# Tauchlampe.net
KiCad netlist of a schematic drawn in EAGLE
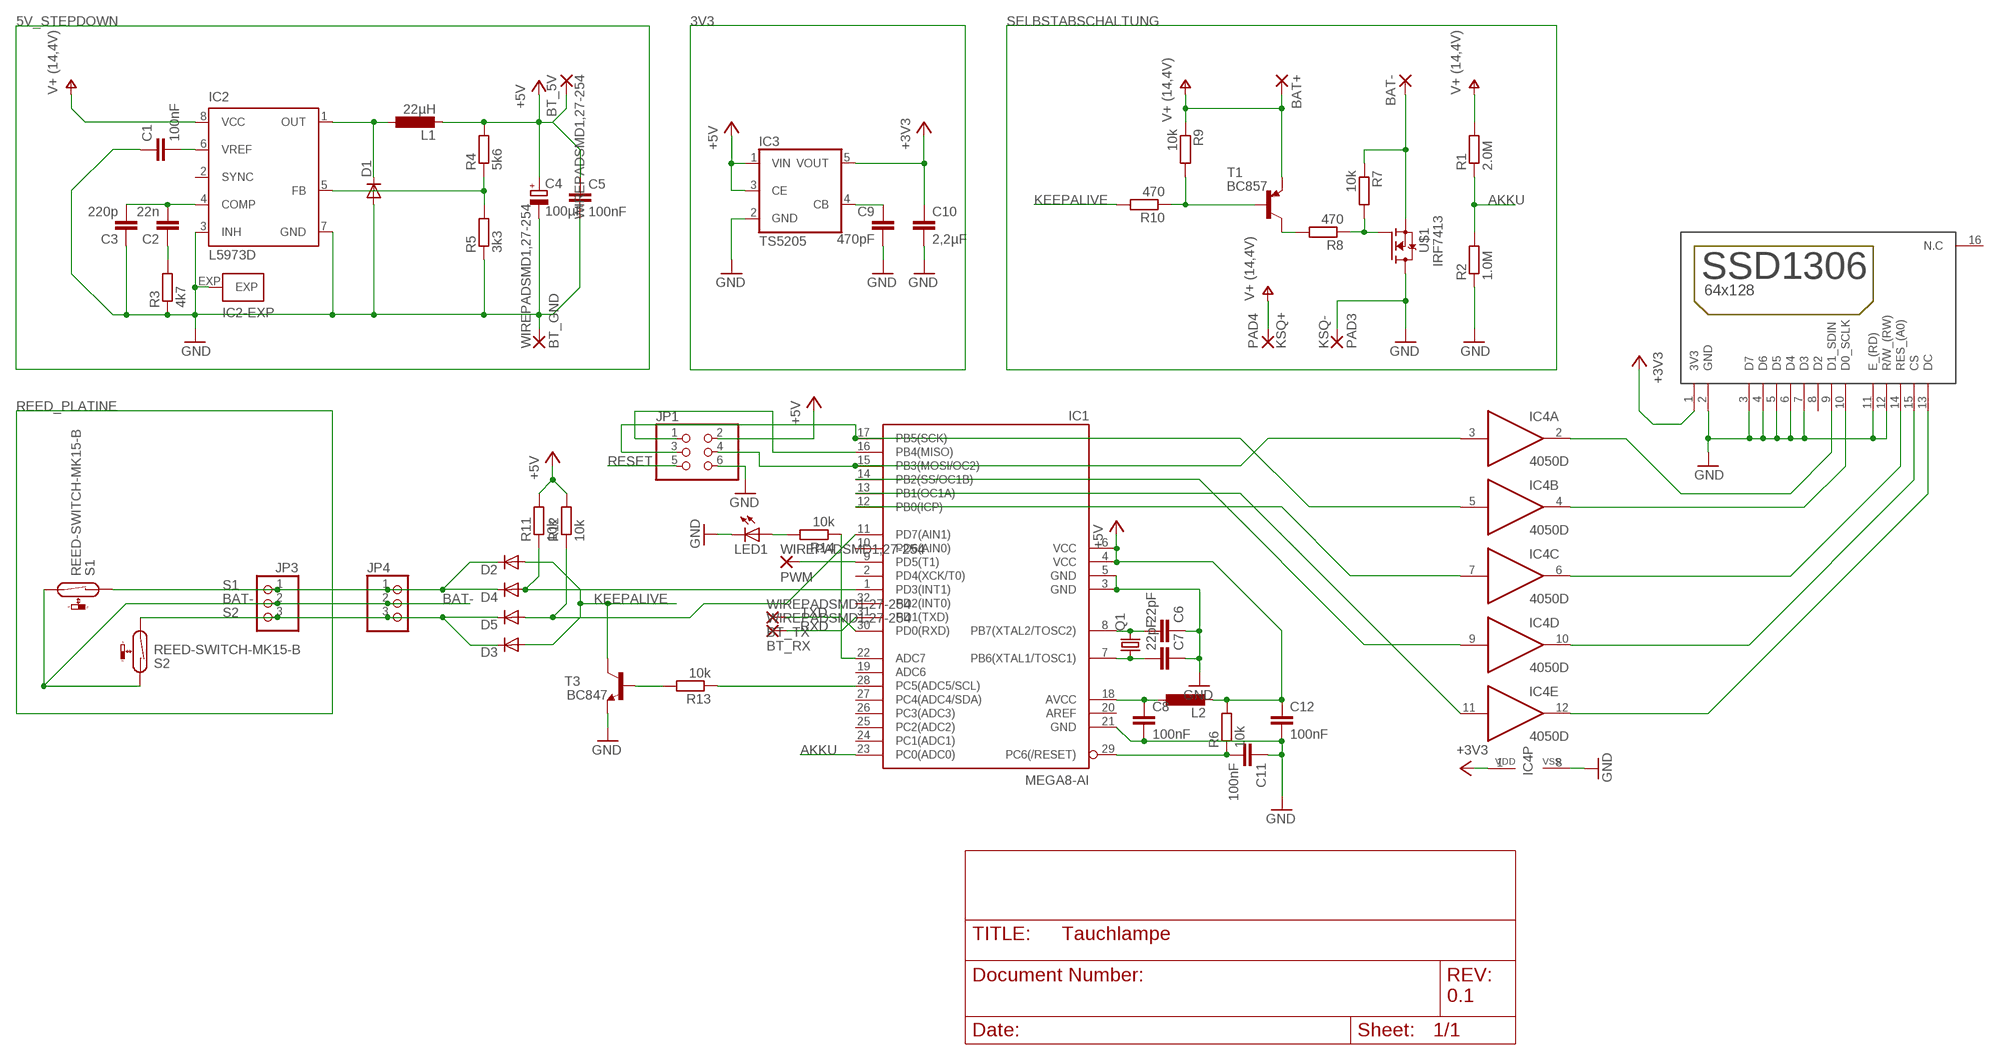
[diagram p0: schematic, sheet 1]

(export (version "E")
  (design (tool "Eeschema 10.0.6"))
  (components
    (comp (ref "BAT+")
      (value "WIREPAD3,81/1,1")
      (footprint "eagle-import:3,81_1,1")
      (libsource (lib "eagle-import") (part "WIREPAD3,81/1,1"))
    )
    (comp (ref "BAT-")
      (value "WIREPAD3,81/1,1")
      (footprint "eagle-import:3,81_1,1")
      (libsource (lib "eagle-import") (part "WIREPAD3,81/1,1"))
    )
    (comp (ref "BT_5V")
      (value "WIREPADSMD1,27-254")
      (footprint "eagle-import:SMD1,27-2,54")
      (libsource (lib "eagle-import") (part "WIREPADSMD1,27-254"))
    )
    (comp (ref "BT_GND")
      (value "WIREPADSMD1,27-254")
      (footprint "eagle-import:SMD1,27-2,54")
      (libsource (lib "eagle-import") (part "WIREPADSMD1,27-254"))
    )
    (comp (ref "BT_RX")
      (value "WIREPADSMD1,27-254")
      (footprint "eagle-import:SMD1,27-2,54")
      (libsource (lib "eagle-import") (part "WIREPADSMD1,27-254"))
    )
    (comp (ref "BT_TX")
      (value "WIREPADSMD1,27-254")
      (footprint "eagle-import:SMD1,27-2,54")
      (libsource (lib "eagle-import") (part "WIREPADSMD1,27-254"))
    )
    (comp (ref "C1")
      (value "100nF")
      (footprint "eagle-import:C0603K")
      (libsource (lib "eagle-import") (part "C-EUC0603K"))
    )
    (comp (ref "C2")
      (value "22n")
      (footprint "eagle-import:C0603K")
      (libsource (lib "eagle-import") (part "C-EUC0603K"))
    )
    (comp (ref "C3")
      (value "220p")
      (footprint "eagle-import:C0603K")
      (libsource (lib "eagle-import") (part "C-EUC0603K"))
    )
    (comp (ref "C4")
      (value "100µF")
      (footprint "eagle-import:153CLV-0505")
      (libsource (lib "eagle-import") (part "CPOL-EU153CLV-0505"))
    )
    (comp (ref "C5")
      (value "100nF")
      (footprint "eagle-import:C1206")
      (libsource (lib "eagle-import") (part "C-EUC1206"))
    )
    (comp (ref "C6")
      (value "22pF")
      (footprint "eagle-import:C1206")
      (libsource (lib "eagle-import") (part "C-EUC1206"))
    )
    (comp (ref "C7")
      (value "22pF")
      (footprint "eagle-import:C1206")
      (libsource (lib "eagle-import") (part "C-EUC1206"))
    )
    (comp (ref "C8")
      (value "100nF")
      (footprint "eagle-import:C0603K")
      (libsource (lib "eagle-import") (part "C-EUC0603K"))
    )
    (comp (ref "C9")
      (value "470pF")
      (footprint "eagle-import:C0603")
      (libsource (lib "eagle-import") (part "C-EUC0603"))
    )
    (comp (ref "C10")
      (value "2,2µF")
      (footprint "eagle-import:C0603")
      (libsource (lib "eagle-import") (part "C-EUC0603"))
    )
    (comp (ref "C11")
      (value "100nF")
      (footprint "eagle-import:C0603K")
      (libsource (lib "eagle-import") (part "C-EUC0603K"))
    )
    (comp (ref "C12")
      (value "100nF")
      (footprint "eagle-import:C0603K")
      (libsource (lib "eagle-import") (part "C-EUC0603K"))
    )
    (comp (ref "D1")
      (value "DIODE-SMB")
      (footprint "eagle-import:SMB")
      (libsource (lib "eagle-import") (part "DIODE-SMB"))
    )
    (comp (ref "D2")
      (value "DIODE-SOD323-W")
      (footprint "eagle-import:SOD323-W")
      (libsource (lib "eagle-import") (part "DIODE-SOD323-W"))
    )
    (comp (ref "D3")
      (value "DIODE-SOD323-W")
      (footprint "eagle-import:SOD323-W")
      (libsource (lib "eagle-import") (part "DIODE-SOD323-W"))
    )
    (comp (ref "D4")
      (value "DIODE-SOD323-W")
      (footprint "eagle-import:SOD323-W")
      (libsource (lib "eagle-import") (part "DIODE-SOD323-W"))
    )
    (comp (ref "D5")
      (value "DIODE-SOD323-W")
      (footprint "eagle-import:SOD323-W")
      (libsource (lib "eagle-import") (part "DIODE-SOD323-W"))
    )
    (comp (ref "IC1")
      (value "MEGA8-AI")
      (footprint "eagle-import:TQFP32-08")
      (fields (field (name "MPN") "ATMEGA8-16AU"))
      (libsource (lib "eagle-import") (part "MEGA8-AI"))
    )
    (comp (ref "IC2")
      (value "L5973D")
      (footprint "eagle-import:HSOP8")
      (fields (field (name "MF") "STMICROELECTRONICS"))
      (libsource (lib "eagle-import") (part "L5973D"))
    )
    (comp (ref "IC3")
      (value "TS5205")
      (footprint "eagle-import:SOT25")
      (libsource (lib "eagle-import") (part "TS5205"))
    )
    (comp (ref "IC4")
      (value "4050D")
      (footprint "eagle-import:SO16")
      (libsource (lib "eagle-import") (part "4050D"))
    )
    (comp (ref "JP1")
      (value "PINHD-2X3")
      (footprint "eagle-import:2X03")
      (libsource (lib "eagle-import") (part "PINHD-2X3"))
    )
    (comp (ref "JP3")
      (value "PINHD-1X03_2.54")
      (footprint "eagle-import:1X03")
      (libsource (lib "eagle-import") (part "PINHD-1X03_2.54"))
    )
    (comp (ref "JP4")
      (value "PINHD-1X03_2.54")
      (footprint "eagle-import:1X03")
      (libsource (lib "eagle-import") (part "PINHD-1X03_2.54"))
    )
    (comp (ref "L1")
      (value "22µH")
      (footprint "eagle-import:PISG")
      (libsource (lib "eagle-import") (part "L-EUPISG"))
    )
    (comp (ref "L2")
      (value "L-EUL2012C")
      (footprint "eagle-import:L2012C")
      (libsource (lib "eagle-import") (part "L-EUL2012C"))
    )
    (comp (ref "LED1")
      (value "LEDCHIP-LED0805")
      (footprint "eagle-import:CHIP-LED0805")
      (libsource (lib "eagle-import") (part "LEDCHIP-LED0805"))
    )
    (comp (ref "PAD3")
      (value "KSQ-")
      (footprint "eagle-import:3,81_1,1")
      (libsource (lib "eagle-import") (part "WIREPAD3,81/1,1"))
    )
    (comp (ref "PAD4")
      (value "KSQ+")
      (footprint "eagle-import:3,81_1,1")
      (libsource (lib "eagle-import") (part "WIREPAD3,81/1,1"))
    )
    (comp (ref "PWM")
      (value "WIREPADSMD1,27-254")
      (footprint "eagle-import:SMD1,27-2,54")
      (libsource (lib "eagle-import") (part "WIREPADSMD1,27-254"))
    )
    (comp (ref "Q1")
      (value "CRYSTALHC49UP")
      (footprint "eagle-import:HC49UP")
      (libsource (lib "eagle-import") (part "CRYSTALHC49UP"))
    )
    (comp (ref "R1")
      (value "2.0M")
      (footprint "eagle-import:M1206")
      (libsource (lib "eagle-import") (part "R-EU_M1206"))
    )
    (comp (ref "R2")
      (value "1.0M")
      (footprint "eagle-import:M1206")
      (libsource (lib "eagle-import") (part "R-EU_M1206"))
    )
    (comp (ref "R3")
      (value "4k7")
      (footprint "eagle-import:R0603")
      (libsource (lib "eagle-import") (part "R-EU_R0603"))
    )
    (comp (ref "R4")
      (value "5k6")
      (footprint "eagle-import:R0603")
      (libsource (lib "eagle-import") (part "R-EU_R0603"))
    )
    (comp (ref "R5")
      (value "3k3")
      (footprint "eagle-import:R0603")
      (libsource (lib "eagle-import") (part "R-EU_R0603"))
    )
    (comp (ref "R6")
      (value "10k")
      (footprint "eagle-import:R1206")
      (libsource (lib "eagle-import") (part "R-EU_R1206"))
    )
    (comp (ref "R7")
      (value "10k")
      (footprint "eagle-import:M0805")
      (libsource (lib "eagle-import") (part "R-EU_M0805"))
    )
    (comp (ref "R8")
      (value "470")
      (footprint "eagle-import:M0805")
      (libsource (lib "eagle-import") (part "R-EU_M0805"))
    )
    (comp (ref "R9")
      (value "10k")
      (footprint "eagle-import:M0805")
      (libsource (lib "eagle-import") (part "R-EU_M0805"))
    )
    (comp (ref "R10")
      (value "470")
      (footprint "eagle-import:M0805")
      (libsource (lib "eagle-import") (part "R-EU_M0805"))
    )
    (comp (ref "R11")
      (value "10k")
      (footprint "eagle-import:M1206")
      (libsource (lib "eagle-import") (part "R-EU_M1206"))
    )
    (comp (ref "R12")
      (value "10k")
      (footprint "eagle-import:M1206")
      (libsource (lib "eagle-import") (part "R-EU_M1206"))
    )
    (comp (ref "R13")
      (value "10k")
      (footprint "eagle-import:M1206")
      (libsource (lib "eagle-import") (part "R-EU_M1206"))
    )
    (comp (ref "R14")
      (value "10k")
      (footprint "eagle-import:M0805")
      (libsource (lib "eagle-import") (part "R-EU_M0805"))
    )
    (comp (ref "S1")
      (value "REED-SWITCH-MK15-B")
      (footprint "eagle-import:MK15")
      (fields (field (name "MF") "MEDER") (field (name "MPN") "MK15-B-2"))
      (libsource (lib "eagle-import") (part "REED-SWITCH-MK15-B"))
    )
    (comp (ref "S2")
      (value "REED-SWITCH-MK15-B")
      (footprint "eagle-import:MK15")
      (fields (field (name "MF") "MEDER") (field (name "MPN") "MK15-B-2"))
      (libsource (lib "eagle-import") (part "REED-SWITCH-MK15-B"))
    )
    (comp (ref "T1")
      (value "BC857")
      (footprint "eagle-import:SOT23-BEC")
      (libsource (lib "eagle-import") (part "-PNP-SOT23-BECBC857A"))
    )
    (comp (ref "T3")
      (value "BC847")
      (footprint "eagle-import:SOT23")
      (libsource (lib "eagle-import") (part "BC847"))
    )
    (comp (ref "U$1")
      (value "IRF7413")
      (footprint "eagle-import:SO-8")
      (libsource (lib "eagle-import") (part "IRF7413"))
    )
    (comp (ref "U$2")
      (value "SDD1306")
      (footprint "eagle-import:2X08")
      (libsource (lib "eagle-import") (part "SDD1306"))
    )
  )
  (nets
    (net (code "1") (name "+3V3") (class "Default")
      (node (ref "C10") (pin "1") (pinfunction "1_1") (pintype "passive"))
      (node (ref "IC3") (pin "5") (pinfunction "VOUT_5") (pintype "passive"))
      (node (ref "IC4") (pin "1") (pinfunction "VDD_1") (pintype "power_in"))
      (node (ref "U$2") (pin "1") (pinfunction "3V3_1") (pintype "bidirectional"))
    )
    (net (code "2") (name "+5V") (class "Default")
      (node (ref "BT_5V") (pin "1") (pinfunction "P_1") (pintype "passive"))
      (node (ref "C12") (pin "1") (pinfunction "1_1") (pintype "passive"))
      (node (ref "C4") (pin "+") (pinfunction "+_+") (pintype "passive"))
      (node (ref "C5") (pin "1") (pinfunction "1_1") (pintype "passive"))
      (node (ref "IC1") (pin "4") (pinfunction "VCC_4") (pintype "power_in"))
      (node (ref "IC1") (pin "6") (pinfunction "VCC_6") (pintype "power_in"))
      (node (ref "IC3") (pin "1") (pinfunction "VIN_1") (pintype "input"))
      (node (ref "IC3") (pin "3") (pinfunction "CE_3") (pintype "input"))
      (node (ref "JP1") (pin "2") (pinfunction "2_2") (pintype "passive"))
      (node (ref "L1") (pin "2") (pinfunction "2_2") (pintype "passive"))
      (node (ref "L2") (pin "2") (pinfunction "2_2") (pintype "passive"))
      (node (ref "R11") (pin "2") (pinfunction "2_2") (pintype "passive"))
      (node (ref "R12") (pin "2") (pinfunction "2_2") (pintype "passive"))
      (node (ref "R4") (pin "2") (pinfunction "2_2") (pintype "passive"))
      (node (ref "R6") (pin "2") (pinfunction "2_2") (pintype "passive"))
    )
    (net (code "5") (name "/AKKU") (class "Default")
      (node (ref "IC1") (pin "23") (pinfunction "PC0(ADC0)_23") (pintype "bidirectional"))
      (node (ref "R1") (pin "1") (pinfunction "1_1") (pintype "passive"))
      (node (ref "R2") (pin "2") (pinfunction "2_2") (pintype "passive"))
    )
    (net (code "6") (name "/BAT-") (class "Default")
      (node (ref "BAT-") (pin "1") (pinfunction "P_1") (pintype "passive"))
      (node (ref "JP3") (pin "2") (pinfunction "2_2") (pintype "passive"))
      (node (ref "JP4") (pin "2") (pinfunction "2_2") (pintype "passive"))
      (node (ref "R7") (pin "1") (pinfunction "1_1") (pintype "passive"))
      (node (ref "S1") (pin "2") (pinfunction "2_2") (pintype "passive"))
      (node (ref "S2") (pin "1") (pinfunction "1_1") (pintype "passive"))
      (node (ref "U$1") (pin "1") (pinfunction "S_1") (pintype "passive"))
      (node (ref "U$1") (pin "2") (pinfunction "S_2") (pintype "passive"))
      (node (ref "U$1") (pin "3") (pinfunction "S_3") (pintype "passive"))
    )
    (net (code "7") (name "/KEEPALIVE") (class "Default")
      (node (ref "D2") (pin "A") (pinfunction "A_A") (pintype "passive"))
      (node (ref "D3") (pin "A") (pinfunction "A_A") (pintype "passive"))
      (node (ref "R10") (pin "2") (pinfunction "2_2") (pintype "passive"))
      (node (ref "T3") (pin "3") (pinfunction "C_3") (pintype "passive"))
    )
    (net (code "9") (name "/RESET") (class "Default")
      (node (ref "C11") (pin "2") (pinfunction "2_2") (pintype "passive"))
      (node (ref "IC1") (pin "29") (pinfunction "PC6(/RESET)_29") (pintype "bidirectional"))
      (node (ref "JP1") (pin "5") (pinfunction "5_5") (pintype "passive"))
      (node (ref "R6") (pin "1") (pinfunction "1_1") (pintype "passive"))
    )
    (net (code "10") (name "/RXD") (class "Default")
      (node (ref "BT_RX") (pin "1") (pinfunction "P_1") (pintype "passive"))
      (node (ref "IC1") (pin "31") (pinfunction "PD1(TXD)_31") (pintype "bidirectional"))
    )
    (net (code "11") (name "/S1") (class "Default")
      (node (ref "D2") (pin "C") (pinfunction "C_C") (pintype "passive"))
      (node (ref "D4") (pin "C") (pinfunction "C_C") (pintype "passive"))
      (node (ref "JP3") (pin "1") (pinfunction "1_1") (pintype "passive"))
      (node (ref "JP4") (pin "1") (pinfunction "1_1") (pintype "passive"))
      (node (ref "S1") (pin "1") (pinfunction "1_1") (pintype "passive"))
    )
    (net (code "12") (name "/S2") (class "Default")
      (node (ref "D3") (pin "C") (pinfunction "C_C") (pintype "passive"))
      (node (ref "D5") (pin "C") (pinfunction "C_C") (pintype "passive"))
      (node (ref "JP3") (pin "3") (pinfunction "3_3") (pintype "passive"))
      (node (ref "JP4") (pin "3") (pinfunction "3_3") (pintype "passive"))
      (node (ref "S2") (pin "2") (pinfunction "2_2") (pintype "passive"))
    )
    (net (code "14") (name "/TXD") (class "Default")
      (node (ref "BT_TX") (pin "1") (pinfunction "P_1") (pintype "passive"))
      (node (ref "IC1") (pin "30") (pinfunction "PD0(RXD)_30") (pintype "bidirectional"))
    )
    (net (code "15") (name "GND") (class "Default")
      (node (ref "BT_GND") (pin "1") (pinfunction "P_1") (pintype "passive"))
      (node (ref "C1") (pin "1") (pinfunction "1_1") (pintype "passive"))
      (node (ref "C10") (pin "2") (pinfunction "2_2") (pintype "passive"))
      (node (ref "C11") (pin "1") (pinfunction "1_1") (pintype "passive"))
      (node (ref "C12") (pin "2") (pinfunction "2_2") (pintype "passive"))
      (node (ref "C3") (pin "1") (pinfunction "1_1") (pintype "passive"))
      (node (ref "C4") (pin "-") (pinfunction "-_-") (pintype "passive"))
      (node (ref "C5") (pin "2") (pinfunction "2_2") (pintype "passive"))
      (node (ref "C6") (pin "1") (pinfunction "1_1") (pintype "passive"))
      (node (ref "C7") (pin "1") (pinfunction "1_1") (pintype "passive"))
      (node (ref "C8") (pin "2") (pinfunction "2_2") (pintype "passive"))
      (node (ref "C9") (pin "2") (pinfunction "2_2") (pintype "passive"))
      (node (ref "D1") (pin "A") (pinfunction "A_A") (pintype "passive"))
      (node (ref "IC1") (pin "21") (pinfunction "GND_21") (pintype "power_in"))
      (node (ref "IC1") (pin "3") (pinfunction "GND_3") (pintype "power_in"))
      (node (ref "IC1") (pin "5") (pinfunction "GND_5") (pintype "power_in"))
      (node (ref "IC2") (pin "3") (pinfunction "INH_3") (pintype "input"))
      (node (ref "IC2") (pin "7") (pinfunction "GND_7") (pintype "power_in"))
      (node (ref "IC2") (pin "EXP") (pinfunction "EXP_EXP") (pintype "input"))
      (node (ref "IC3") (pin "2") (pinfunction "GND_2") (pintype "passive"))
      (node (ref "IC4") (pin "8") (pinfunction "VSS_8") (pintype "power_in"))
      (node (ref "JP1") (pin "6") (pinfunction "6_6") (pintype "passive"))
      (node (ref "LED1") (pin "C") (pinfunction "C_C") (pintype "passive"))
      (node (ref "PAD3") (pin "1") (pinfunction "P_1") (pintype "passive"))
      (node (ref "R2") (pin "1") (pinfunction "1_1") (pintype "passive"))
      (node (ref "R3") (pin "1") (pinfunction "1_1") (pintype "passive"))
      (node (ref "R5") (pin "1") (pinfunction "1_1") (pintype "passive"))
      (node (ref "T3") (pin "2") (pinfunction "E_2") (pintype "passive"))
      (node (ref "U$1") (pin "5") (pinfunction "D_5") (pintype "passive"))
      (node (ref "U$1") (pin "6") (pinfunction "D_6") (pintype "passive"))
      (node (ref "U$1") (pin "7") (pinfunction "D_7") (pintype "passive"))
      (node (ref "U$1") (pin "8") (pinfunction "D_8") (pintype "passive"))
      (node (ref "U$2") (pin "11") (pinfunction "E_(RD)_11") (pintype "bidirectional"))
      (node (ref "U$2") (pin "12") (pinfunction "R/W_(RW)_12") (pintype "bidirectional"))
      (node (ref "U$2") (pin "2") (pinfunction "GND_2") (pintype "bidirectional"))
      (node (ref "U$2") (pin "3") (pinfunction "D7_3") (pintype "bidirectional"))
      (node (ref "U$2") (pin "4") (pinfunction "D6_4") (pintype "bidirectional"))
      (node (ref "U$2") (pin "5") (pinfunction "D5_5") (pintype "bidirectional"))
      (node (ref "U$2") (pin "6") (pinfunction "D4_6") (pintype "bidirectional"))
      (node (ref "U$2") (pin "7") (pinfunction "D3_7") (pintype "bidirectional"))
    )
    (net (code "16") (name "Net-(C2-Pad1)") (class "Default")
      (node (ref "C2") (pin "1") (pinfunction "1_1") (pintype "passive"))
      (node (ref "R3") (pin "2") (pinfunction "2_2") (pintype "passive"))
    )
    (net (code "17") (name "Net-(IC1-ADC7)") (class "Default")
      (node (ref "IC1") (pin "22") (pinfunction "ADC7_22") (pintype "bidirectional"))
      (node (ref "R14") (pin "1") (pinfunction "1_1") (pintype "passive"))
    )
    (net (code "18") (name "Net-(IC1-AVCC)") (class "Default")
      (node (ref "C8") (pin "1") (pinfunction "1_1") (pintype "passive"))
      (node (ref "IC1") (pin "18") (pinfunction "AVCC_18") (pintype "power_in"))
      (node (ref "L2") (pin "1") (pinfunction "1_1") (pintype "passive"))
    )
    (net (code "19") (name "Net-(IC1-PB0(ICP))") (class "Default")
      (node (ref "IC1") (pin "12") (pinfunction "PB0(ICP)_12") (pintype "bidirectional"))
      (node (ref "IC4") (pin "7") (pinfunction "I_7") (pintype "input"))
    )
    (net (code "20") (name "Net-(IC1-PB1(OC1A))") (class "Default")
      (node (ref "IC1") (pin "13") (pinfunction "PB1(OC1A)_13") (pintype "bidirectional"))
      (node (ref "IC4") (pin "11") (pinfunction "I_11") (pintype "input"))
    )
    (net (code "21") (name "Net-(IC1-PB2(SS{slash}OC1B))") (class "Default")
      (node (ref "IC1") (pin "14") (pinfunction "PB2(SS/OC1B)_14") (pintype "bidirectional"))
      (node (ref "IC4") (pin "9") (pinfunction "I_9") (pintype "input"))
    )
    (net (code "22") (name "Net-(IC1-PB3(MOSI{slash}OC2))") (class "Default")
      (node (ref "IC1") (pin "15") (pinfunction "PB3(MOSI/OC2)_15") (pintype "bidirectional"))
      (node (ref "IC4") (pin "3") (pinfunction "I_3") (pintype "input"))
      (node (ref "JP1") (pin "4") (pinfunction "4_4") (pintype "passive"))
    )
    (net (code "23") (name "Net-(IC1-PB4(MISO))") (class "Default")
      (node (ref "IC1") (pin "16") (pinfunction "PB4(MISO)_16") (pintype "bidirectional"))
      (node (ref "JP1") (pin "1") (pinfunction "1_1") (pintype "passive"))
    )
    (net (code "24") (name "Net-(IC1-PB5(SCK))") (class "Default")
      (node (ref "IC1") (pin "17") (pinfunction "PB5(SCK)_17") (pintype "bidirectional"))
      (node (ref "IC4") (pin "5") (pinfunction "I_5") (pintype "input"))
      (node (ref "JP1") (pin "3") (pinfunction "3_3") (pintype "passive"))
    )
    (net (code "25") (name "Net-(IC1-PB6(XTAL1{slash}TOSC1))") (class "Default")
      (node (ref "C7") (pin "2") (pinfunction "2_2") (pintype "passive"))
      (node (ref "IC1") (pin "7") (pinfunction "PB6(XTAL1/TOSC1)_7") (pintype "bidirectional"))
      (node (ref "Q1") (pin "1") (pinfunction "1_1") (pintype "passive"))
    )
    (net (code "26") (name "Net-(IC1-PB7(XTAL2{slash}TOSC2))") (class "Default")
      (node (ref "C6") (pin "2") (pinfunction "2_2") (pintype "passive"))
      (node (ref "IC1") (pin "8") (pinfunction "PB7(XTAL2/TOSC2)_8") (pintype "bidirectional"))
      (node (ref "Q1") (pin "2") (pinfunction "2_2") (pintype "passive"))
    )
    (net (code "27") (name "Net-(IC1-PC5(ADC5{slash}SCL))") (class "Default")
      (node (ref "IC1") (pin "28") (pinfunction "PC5(ADC5/SCL)_28") (pintype "bidirectional"))
      (node (ref "R13") (pin "1") (pinfunction "1_1") (pintype "passive"))
    )
    (net (code "28") (name "Net-(IC1-PD3(INT1))") (class "Default")
      (node (ref "D4") (pin "A") (pinfunction "A_A") (pintype "passive"))
      (node (ref "IC1") (pin "1") (pinfunction "PD3(INT1)_1") (pintype "bidirectional"))
      (node (ref "R11") (pin "1") (pinfunction "1_1") (pintype "passive"))
    )
    (net (code "29") (name "Net-(IC1-PD5(T1))") (class "Default")
      (node (ref "IC1") (pin "9") (pinfunction "PD5(T1)_9") (pintype "bidirectional"))
      (node (ref "PWM") (pin "1") (pinfunction "P_1") (pintype "passive"))
    )
    (net (code "30") (name "Net-(IC1-PD7(AIN1))") (class "Default")
      (node (ref "D5") (pin "A") (pinfunction "A_A") (pintype "passive"))
      (node (ref "IC1") (pin "11") (pinfunction "PD7(AIN1)_11") (pintype "bidirectional"))
      (node (ref "R12") (pin "1") (pinfunction "1_1") (pintype "passive"))
    )
    (net (code "31") (name "Net-(IC2B-COMP)") (class "Default")
      (node (ref "C2") (pin "2") (pinfunction "2_2") (pintype "passive"))
      (node (ref "C3") (pin "2") (pinfunction "2_2") (pintype "passive"))
      (node (ref "IC2") (pin "4") (pinfunction "COMP_4") (pintype "passive"))
    )
    (net (code "32") (name "Net-(IC2B-FB)") (class "Default")
      (node (ref "IC2") (pin "5") (pinfunction "FB_5") (pintype "input"))
      (node (ref "R4") (pin "1") (pinfunction "1_1") (pintype "passive"))
      (node (ref "R5") (pin "2") (pinfunction "2_2") (pintype "passive"))
    )
    (net (code "33") (name "Net-(IC2B-OUT)") (class "Default")
      (node (ref "D1") (pin "C") (pinfunction "C_C") (pintype "passive"))
      (node (ref "IC2") (pin "1") (pinfunction "OUT_1") (pintype "output"))
      (node (ref "L1") (pin "1") (pinfunction "1_1") (pintype "passive"))
    )
    (net (code "34") (name "Net-(IC2B-VREF)") (class "Default")
      (node (ref "C1") (pin "2") (pinfunction "2_2") (pintype "passive"))
      (node (ref "IC2") (pin "6") (pinfunction "VREF_6") (pintype "input"))
    )
    (net (code "35") (name "Net-(IC3-CB)") (class "Default")
      (node (ref "C9") (pin "1") (pinfunction "1_1") (pintype "passive"))
      (node (ref "IC3") (pin "4") (pinfunction "CB_4") (pintype "input"))
    )
    (net (code "36") (name "Net-(IC4A-O)") (class "Default")
      (node (ref "IC4") (pin "2") (pinfunction "O_2") (pintype "output"))
      (node (ref "U$2") (pin "9") (pinfunction "D1_SDIN_9") (pintype "bidirectional"))
    )
    (net (code "37") (name "Net-(IC4B-O)") (class "Default")
      (node (ref "IC4") (pin "4") (pinfunction "O_4") (pintype "output"))
      (node (ref "U$2") (pin "10") (pinfunction "D0_SCLK_10") (pintype "bidirectional"))
    )
    (net (code "38") (name "Net-(IC4C-O)") (class "Default")
      (node (ref "IC4") (pin "6") (pinfunction "O_6") (pintype "output"))
      (node (ref "U$2") (pin "14") (pinfunction "RES_(A0)_14") (pintype "bidirectional"))
    )
    (net (code "39") (name "Net-(IC4D-O)") (class "Default")
      (node (ref "IC4") (pin "10") (pinfunction "O_10") (pintype "output"))
      (node (ref "U$2") (pin "15") (pinfunction "CS_15") (pintype "bidirectional"))
    )
    (net (code "40") (name "Net-(IC4E-O)") (class "Default")
      (node (ref "IC4") (pin "12") (pinfunction "O_12") (pintype "output"))
      (node (ref "U$2") (pin "13") (pinfunction "DC_13") (pintype "bidirectional"))
    )
    (net (code "41") (name "Net-(LED1-PadA)") (class "Default")
      (node (ref "LED1") (pin "A") (pinfunction "A_A") (pintype "passive"))
      (node (ref "R14") (pin "2") (pinfunction "2_2") (pintype "passive"))
    )
    (net (code "42") (name "Net-(R8-Pad2)") (class "Default")
      (node (ref "R8") (pin "2") (pinfunction "2_2") (pintype "passive"))
      (node (ref "T1") (pin "C") (pinfunction "C_C") (pintype "passive"))
    )
    (net (code "43") (name "Net-(R10-Pad1)") (class "Default")
      (node (ref "R10") (pin "1") (pinfunction "1_1") (pintype "passive"))
      (node (ref "R9") (pin "2") (pinfunction "2_2") (pintype "passive"))
      (node (ref "T1") (pin "B") (pinfunction "B_B") (pintype "passive"))
    )
    (net (code "44") (name "Net-(T3-B)") (class "Default")
      (node (ref "R13") (pin "2") (pinfunction "2_2") (pintype "passive"))
      (node (ref "T3") (pin "1") (pinfunction "B_1") (pintype "passive"))
    )
    (net (code "45") (name "Net-(U$1-G)") (class "Default")
      (node (ref "R7") (pin "2") (pinfunction "2_2") (pintype "passive"))
      (node (ref "R8") (pin "1") (pinfunction "1_1") (pintype "passive"))
      (node (ref "U$1") (pin "4") (pinfunction "G_4") (pintype "passive"))
    )
    (net (code "46") (name "V+ (14,4V)") (class "Default")
      (node (ref "BAT+") (pin "1") (pinfunction "P_1") (pintype "passive"))
      (node (ref "IC2") (pin "8") (pinfunction "VCC_8") (pintype "input"))
      (node (ref "PAD4") (pin "1") (pinfunction "P_1") (pintype "passive"))
      (node (ref "R1") (pin "2") (pinfunction "2_2") (pintype "passive"))
      (node (ref "R9") (pin "1") (pinfunction "1_1") (pintype "passive"))
      (node (ref "T1") (pin "E") (pinfunction "E_E") (pintype "passive"))
    )
    (net (code "47") (name "unconnected-(IC1-ADC6-Pad19)") (class "Default")
      (node (ref "IC1") (pin "19") (pinfunction "ADC6_19") (pintype "bidirectional"))
    )
    (net (code "48") (name "unconnected-(IC1-AREF-Pad20)") (class "Default")
      (node (ref "IC1") (pin "20") (pinfunction "AREF_20") (pintype "passive"))
    )
    (net (code "49") (name "unconnected-(IC1-PC1(ADC1)-Pad24)") (class "Default")
      (node (ref "IC1") (pin "24") (pinfunction "PC1(ADC1)_24") (pintype "bidirectional"))
    )
    (net (code "50") (name "unconnected-(IC1-PC2(ADC2)-Pad25)") (class "Default")
      (node (ref "IC1") (pin "25") (pinfunction "PC2(ADC2)_25") (pintype "bidirectional"))
    )
    (net (code "51") (name "unconnected-(IC1-PC3(ADC3)-Pad26)") (class "Default")
      (node (ref "IC1") (pin "26") (pinfunction "PC3(ADC3)_26") (pintype "bidirectional"))
    )
    (net (code "52") (name "unconnected-(IC1-PC4(ADC4{slash}SDA)-Pad27)") (class "Default")
      (node (ref "IC1") (pin "27") (pinfunction "PC4(ADC4/SDA)_27") (pintype "bidirectional"))
    )
    (net (code "53") (name "unconnected-(IC1-PD2(INT0)-Pad32)") (class "Default")
      (node (ref "IC1") (pin "32") (pinfunction "PD2(INT0)_32") (pintype "bidirectional"))
    )
    (net (code "54") (name "unconnected-(IC1-PD4(XCK{slash}T0)-Pad2)") (class "Default")
      (node (ref "IC1") (pin "2") (pinfunction "PD4(XCK/T0)_2") (pintype "bidirectional"))
    )
    (net (code "55") (name "unconnected-(IC1-PD6(AIN0)-Pad10)") (class "Default")
      (node (ref "IC1") (pin "10") (pinfunction "PD6(AIN0)_10") (pintype "bidirectional"))
    )
    (net (code "56") (name "unconnected-(IC2B-SYNC-Pad2)") (class "Default")
      (node (ref "IC2") (pin "2") (pinfunction "SYNC_2") (pintype "input"))
    )
    (net (code "57") (name "unconnected-(U$2-D2-Pad8)") (class "Default")
      (node (ref "U$2") (pin "8") (pinfunction "D2_8") (pintype "bidirectional"))
    )
    (net (code "58") (name "unconnected-(U$2-N.C-Pad16)") (class "Default")
      (node (ref "U$2") (pin "16") (pinfunction "N.C_16") (pintype "bidirectional"))
    )
  )
)
